# paige.net
KiCad netlist of a schematic drawn in EAGLE
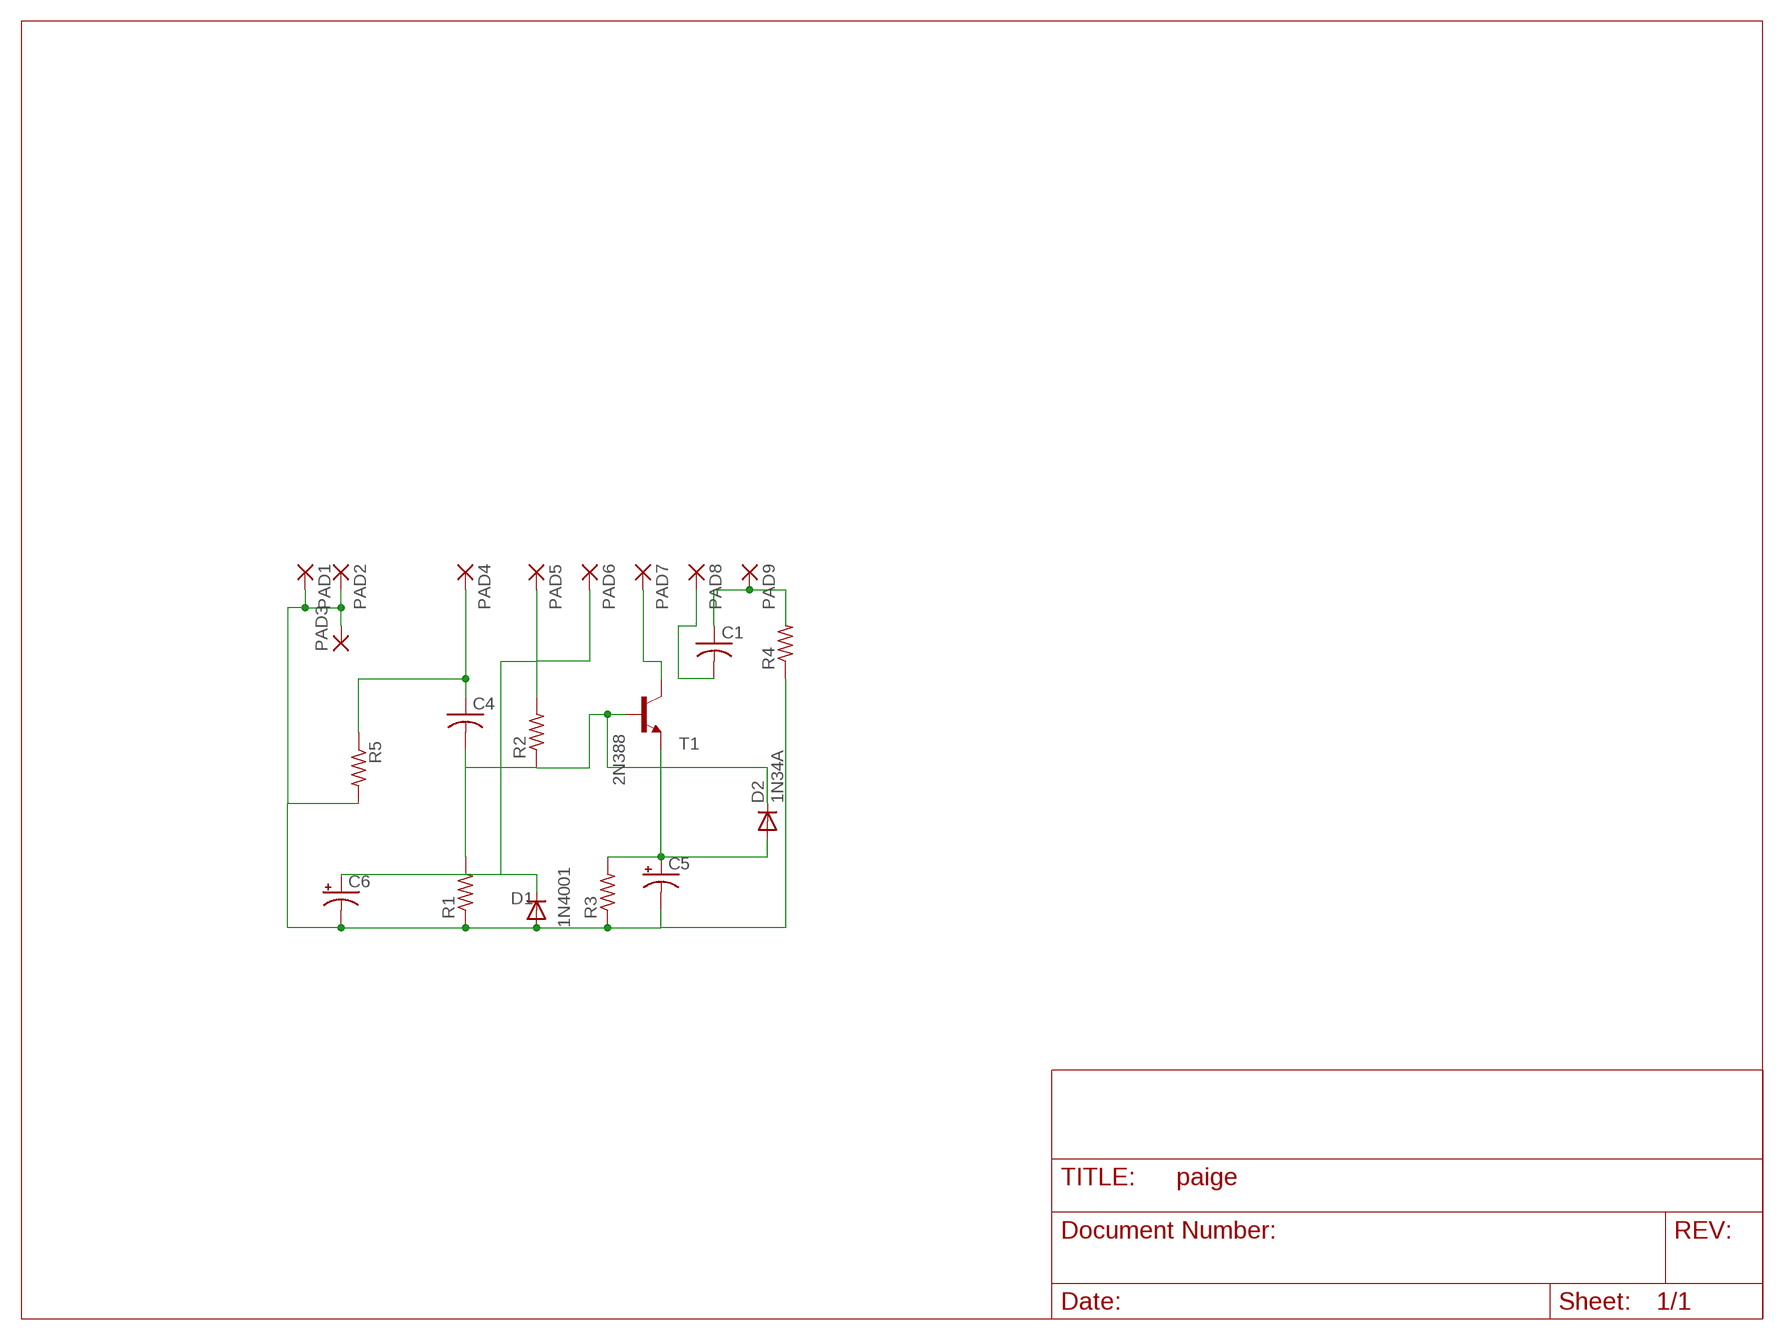
[diagram p0: schematic, sheet 1]

(export (version "E")
  (design (tool "Eeschema 10.0.6"))
  (components
    (comp (ref "C1")
      (value "C-US025-050X050")
      (footprint "eagle-import:C025-050X050")
      (libsource (lib "eagle-import") (part "C-US025-050X050"))
    )
    (comp (ref "C4")
      (value "C-US075-032X103")
      (footprint "eagle-import:C075-032X103")
      (libsource (lib "eagle-import") (part "C-US075-032X103"))
    )
    (comp (ref "C5")
      (value "CPOL-USE2.5-7")
      (footprint "eagle-import:E2,5-7")
      (libsource (lib "eagle-import") (part "CPOL-USE2.5-7"))
    )
    (comp (ref "C6")
      (value "CPOL-USE2.5-7")
      (footprint "eagle-import:E2,5-7")
      (libsource (lib "eagle-import") (part "CPOL-USE2.5-7"))
    )
    (comp (ref "D1")
      (value "1N4001")
      (footprint "eagle-import:DO41-10")
      (libsource (lib "eagle-import") (part "1N4004"))
    )
    (comp (ref "D2")
      (value "1N34A")
      (footprint "eagle-import:DO41-10")
      (libsource (lib "eagle-import") (part "1N4004"))
    )
    (comp (ref "PAD1")
      (value "1,6/0,9")
      (footprint "eagle-import:1,6_0,9")
      (libsource (lib "eagle-import") (part "1,6/0,9"))
    )
    (comp (ref "PAD2")
      (value "1,6/0,9")
      (footprint "eagle-import:1,6_0,9")
      (libsource (lib "eagle-import") (part "1,6/0,9"))
    )
    (comp (ref "PAD3")
      (value "1,6/0,9")
      (footprint "eagle-import:1,6_0,9")
      (libsource (lib "eagle-import") (part "1,6/0,9"))
    )
    (comp (ref "PAD4")
      (value "1,6/0,9")
      (footprint "eagle-import:1,6_0,9")
      (libsource (lib "eagle-import") (part "1,6/0,9"))
    )
    (comp (ref "PAD5")
      (value "1,6/0,9")
      (footprint "eagle-import:1,6_0,9")
      (libsource (lib "eagle-import") (part "1,6/0,9"))
    )
    (comp (ref "PAD6")
      (value "1,6/0,9")
      (footprint "eagle-import:1,6_0,9")
      (libsource (lib "eagle-import") (part "1,6/0,9"))
    )
    (comp (ref "PAD7")
      (value "1,6/0,9")
      (footprint "eagle-import:1,6_0,9")
      (libsource (lib "eagle-import") (part "1,6/0,9"))
    )
    (comp (ref "PAD8")
      (value "1,6/0,9")
      (footprint "eagle-import:1,6_0,9")
      (libsource (lib "eagle-import") (part "1,6/0,9"))
    )
    (comp (ref "PAD9")
      (value "1,6/0,9")
      (footprint "eagle-import:1,6_0,9")
      (libsource (lib "eagle-import") (part "1,6/0,9"))
    )
    (comp (ref "R1")
      (value "R-US_0207/5V")
      (footprint "eagle-import:0207_5V")
      (libsource (lib "eagle-import") (part "R-US_0207/5V"))
    )
    (comp (ref "R2")
      (value "R-US_0207/5V")
      (footprint "eagle-import:0207_5V")
      (libsource (lib "eagle-import") (part "R-US_0207/5V"))
    )
    (comp (ref "R3")
      (value "R-US_0207/5V")
      (footprint "eagle-import:0207_5V")
      (libsource (lib "eagle-import") (part "R-US_0207/5V"))
    )
    (comp (ref "R4")
      (value "R-US_0207/5V")
      (footprint "eagle-import:0207_5V")
      (libsource (lib "eagle-import") (part "R-US_0207/5V"))
    )
    (comp (ref "R5")
      (value "R-US_0207/5V")
      (footprint "eagle-import:0207_5V")
      (libsource (lib "eagle-import") (part "R-US_0207/5V"))
    )
    (comp (ref "T1")
      (value "2N388")
      (footprint "eagle-import:TO92-EBC-OVAL")
      (libsource (lib "eagle-import") (part "2N2222"))
    )
  )
  (nets
    (net (code "1") (name "Net-(C4-Pad2)") (class "Default")
      (node (ref "C4") (pin "2") (pinfunction "2_2") (pintype "passive"))
      (node (ref "D2") (pin "C") (pinfunction "C_C") (pintype "passive"))
      (node (ref "R1") (pin "2") (pinfunction "2_2") (pintype "passive"))
      (node (ref "R2") (pin "1") (pinfunction "1_1") (pintype "passive"))
      (node (ref "T1") (pin "B") (pinfunction "B_B") (pintype "passive"))
    )
    (net (code "2") (name "Net-(C5-Pad+)") (class "Default")
      (node (ref "C5") (pin "+") (pinfunction "+_+") (pintype "passive"))
      (node (ref "D2") (pin "A") (pinfunction "A_A") (pintype "passive"))
      (node (ref "R3") (pin "2") (pinfunction "2_2") (pintype "passive"))
      (node (ref "T1") (pin "E") (pinfunction "E_E") (pintype "passive"))
    )
    (net (code "3") (name "Net-(PAD1-P)") (class "Default")
      (node (ref "C5") (pin "-") (pinfunction "-_-") (pintype "passive"))
      (node (ref "C6") (pin "-") (pinfunction "-_-") (pintype "passive"))
      (node (ref "D1") (pin "A") (pinfunction "A_A") (pintype "passive"))
      (node (ref "PAD1") (pin "1") (pinfunction "P_1") (pintype "passive"))
      (node (ref "PAD2") (pin "1") (pinfunction "P_1") (pintype "passive"))
      (node (ref "PAD3") (pin "1") (pinfunction "P_1") (pintype "passive"))
      (node (ref "R1") (pin "1") (pinfunction "1_1") (pintype "passive"))
      (node (ref "R3") (pin "1") (pinfunction "1_1") (pintype "passive"))
      (node (ref "R4") (pin "1") (pinfunction "1_1") (pintype "passive"))
      (node (ref "R5") (pin "2") (pinfunction "2_2") (pintype "passive"))
    )
    (net (code "4") (name "Net-(PAD4-P)") (class "Default")
      (node (ref "C4") (pin "1") (pinfunction "1_1") (pintype "passive"))
      (node (ref "PAD4") (pin "1") (pinfunction "P_1") (pintype "passive"))
      (node (ref "R5") (pin "1") (pinfunction "1_1") (pintype "passive"))
    )
    (net (code "5") (name "Net-(PAD5-P)") (class "Default")
      (node (ref "C6") (pin "+") (pinfunction "+_+") (pintype "passive"))
      (node (ref "D1") (pin "C") (pinfunction "C_C") (pintype "passive"))
      (node (ref "PAD5") (pin "1") (pinfunction "P_1") (pintype "passive"))
      (node (ref "PAD6") (pin "1") (pinfunction "P_1") (pintype "passive"))
      (node (ref "R2") (pin "2") (pinfunction "2_2") (pintype "passive"))
    )
    (net (code "6") (name "Net-(PAD7-P)") (class "Default")
      (node (ref "PAD7") (pin "1") (pinfunction "P_1") (pintype "passive"))
      (node (ref "T1") (pin "C") (pinfunction "C_C") (pintype "passive"))
    )
    (net (code "7") (name "Net-(PAD8-P)") (class "Default")
      (node (ref "C1") (pin "2") (pinfunction "2_2") (pintype "passive"))
      (node (ref "PAD8") (pin "1") (pinfunction "P_1") (pintype "passive"))
    )
    (net (code "8") (name "Net-(PAD9-P)") (class "Default")
      (node (ref "C1") (pin "1") (pinfunction "1_1") (pintype "passive"))
      (node (ref "PAD9") (pin "1") (pinfunction "P_1") (pintype "passive"))
      (node (ref "R4") (pin "2") (pinfunction "2_2") (pintype "passive"))
    )
  )
)
